# RFBoardLayoutGen0_v03_1_1_clean.net
KiCad netlist of a schematic drawn in EAGLE
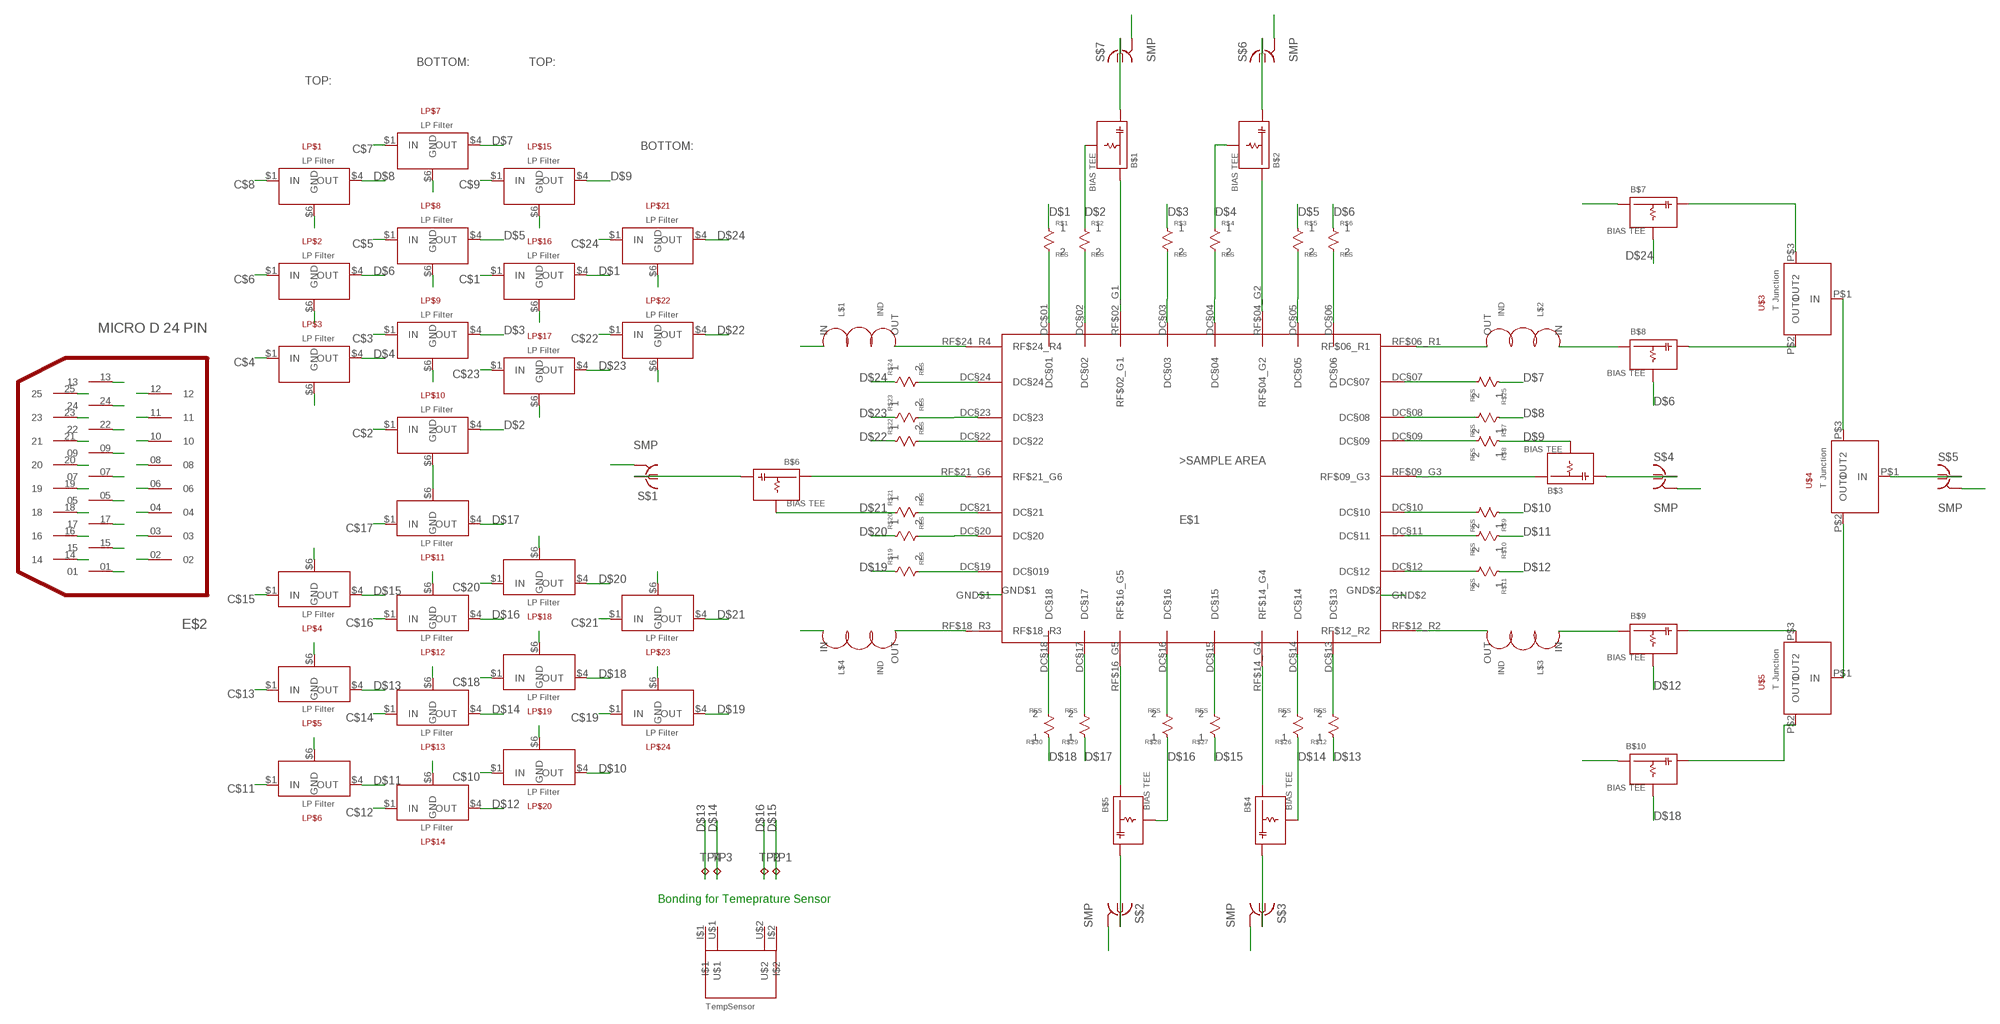
[diagram p0: schematic, sheet 1, part 1 of 2]
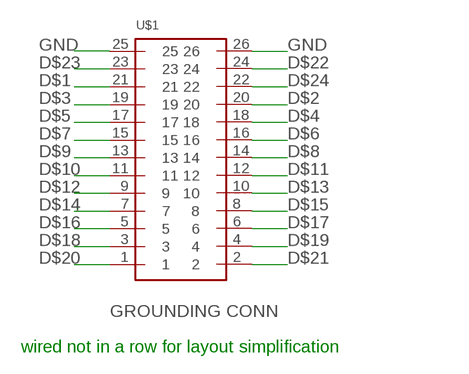
[diagram p1: schematic, sheet 1, part 2 of 2]

(export (version "E")
  (design (tool "Eeschema 10.0.6"))
  (components
    (comp (ref "B$1")
      (value "BIASTEEDOWN")
      (footprint "eagle-import:BIAS_TEE_DOWN_0603")
      (libsource (lib "eagle-import") (part "BIASTEEDOWN"))
    )
    (comp (ref "B$2")
      (value "BIASTEEUP")
      (footprint "eagle-import:BIAS_TEE_UP_0603")
      (libsource (lib "eagle-import") (part "BIASTEEUP"))
    )
    (comp (ref "B$3")
      (value "BIASTEEDOWN")
      (footprint "eagle-import:BIAS_TEE_DOWN_0603")
      (libsource (lib "eagle-import") (part "BIASTEEDOWN"))
    )
    (comp (ref "B$4")
      (value "BIASTEEDOWN")
      (footprint "eagle-import:BIAS_TEE_DOWN_0603")
      (libsource (lib "eagle-import") (part "BIASTEEDOWN"))
    )
    (comp (ref "B$5")
      (value "BIASTEEUP")
      (footprint "eagle-import:BIAS_TEE_UP_0603")
      (libsource (lib "eagle-import") (part "BIASTEEUP"))
    )
    (comp (ref "B$6")
      (value "BIASTEEDOWN")
      (footprint "eagle-import:BIAS_TEE_DOWN_0603")
      (libsource (lib "eagle-import") (part "BIASTEEDOWN"))
    )
    (comp (ref "B$7")
      (value "BIASTEEUP")
      (footprint "eagle-import:BIAS_TEE_UP_0603")
      (libsource (lib "eagle-import") (part "BIASTEEUP"))
    )
    (comp (ref "B$8")
      (value "BIASTEEDOWN")
      (footprint "eagle-import:BIAS_TEE_DOWN_0603")
      (libsource (lib "eagle-import") (part "BIASTEEDOWN"))
    )
    (comp (ref "B$9")
      (value "BIASTEEUP")
      (footprint "eagle-import:BIAS_TEE_UP_0603")
      (libsource (lib "eagle-import") (part "BIASTEEUP"))
    )
    (comp (ref "B$10")
      (value "BIASTEEDOWN")
      (footprint "eagle-import:BIAS_TEE_DOWN_0603")
      (libsource (lib "eagle-import") (part "BIASTEEDOWN"))
    )
    (comp (ref "E$1")
      (value "24DC+10RF")
      (footprint "eagle-import:24DC+10RF_400MU-PADS_0.7X0.7_V1.0")
      (libsource (lib "eagle-import") (part "24DC+10RF"))
    )
    (comp (ref "E$2")
      (value "25_SOCKET_M83513(13-DPINOUT2")
      (footprint "eagle-import:25_SOCKET_M83513_13-D_V2")
      (libsource (lib "eagle-import") (part "25_SOCKET_M83513(13-DPINOUT2"))
    )
    (comp (ref "L$1")
      (value "L_MATCH")
      (footprint "eagle-import:L_MATCH")
      (libsource (lib "eagle-import") (part "L_MATCH"))
    )
    (comp (ref "L$2")
      (value "L_MATCH")
      (footprint "eagle-import:L_MATCH")
      (libsource (lib "eagle-import") (part "L_MATCH"))
    )
    (comp (ref "L$3")
      (value "L_MATCH")
      (footprint "eagle-import:L_MATCH")
      (libsource (lib "eagle-import") (part "L_MATCH"))
    )
    (comp (ref "L$4")
      (value "L_MATCH")
      (footprint "eagle-import:L_MATCH")
      (libsource (lib "eagle-import") (part "L_MATCH"))
    )
    (comp (ref "LP$1")
      (value "LP-FILTER/1-STAGETOP")
      (footprint "eagle-import:LP-FILTER_1_STAGE_OS_0603_TOP")
      (libsource (lib "eagle-import") (part "LP-FILTER/1-STAGETOP"))
    )
    (comp (ref "LP$2")
      (value "LP-FILTER/1-STAGETOP")
      (footprint "eagle-import:LP-FILTER_1_STAGE_OS_0603_TOP")
      (libsource (lib "eagle-import") (part "LP-FILTER/1-STAGETOP"))
    )
    (comp (ref "LP$3")
      (value "LP-FILTER/1-STAGETOP")
      (footprint "eagle-import:LP-FILTER_1_STAGE_OS_0603_TOP")
      (libsource (lib "eagle-import") (part "LP-FILTER/1-STAGETOP"))
    )
    (comp (ref "LP$4")
      (value "LP-FILTER/1-STAGETOP")
      (footprint "eagle-import:LP-FILTER_1_STAGE_OS_0603_TOP")
      (libsource (lib "eagle-import") (part "LP-FILTER/1-STAGETOP"))
    )
    (comp (ref "LP$5")
      (value "LP-FILTER/1-STAGETOP")
      (footprint "eagle-import:LP-FILTER_1_STAGE_OS_0603_TOP")
      (libsource (lib "eagle-import") (part "LP-FILTER/1-STAGETOP"))
    )
    (comp (ref "LP$6")
      (value "LP-FILTER/1-STAGETOP")
      (footprint "eagle-import:LP-FILTER_1_STAGE_OS_0603_TOP")
      (libsource (lib "eagle-import") (part "LP-FILTER/1-STAGETOP"))
    )
    (comp (ref "LP$7")
      (value "LP-FILTER/1-STAGEBOT")
      (footprint "eagle-import:LP-FILTER_1_STAGE_OS_0603_BOTTOM")
      (libsource (lib "eagle-import") (part "LP-FILTER/1-STAGEBOT"))
    )
    (comp (ref "LP$8")
      (value "LP-FILTER/1-STAGEBOT")
      (footprint "eagle-import:LP-FILTER_1_STAGE_OS_0603_BOTTOM")
      (libsource (lib "eagle-import") (part "LP-FILTER/1-STAGEBOT"))
    )
    (comp (ref "LP$9")
      (value "LP-FILTER/1-STAGEBOT")
      (footprint "eagle-import:LP-FILTER_1_STAGE_OS_0603_BOTTOM")
      (libsource (lib "eagle-import") (part "LP-FILTER/1-STAGEBOT"))
    )
    (comp (ref "LP$10")
      (value "LP-FILTER/1-STAGEBOT")
      (footprint "eagle-import:LP-FILTER_1_STAGE_OS_0603_BOTTOM")
      (libsource (lib "eagle-import") (part "LP-FILTER/1-STAGEBOT"))
    )
    (comp (ref "LP$11")
      (value "LP-FILTER/1-STAGEBOT")
      (footprint "eagle-import:LP-FILTER_1_STAGE_OS_0603_BOTTOM")
      (libsource (lib "eagle-import") (part "LP-FILTER/1-STAGEBOT"))
    )
    (comp (ref "LP$12")
      (value "LP-FILTER/1-STAGEBOT")
      (footprint "eagle-import:LP-FILTER_1_STAGE_OS_0603_BOTTOM")
      (libsource (lib "eagle-import") (part "LP-FILTER/1-STAGEBOT"))
    )
    (comp (ref "LP$13")
      (value "LP-FILTER/1-STAGEBOT")
      (footprint "eagle-import:LP-FILTER_1_STAGE_OS_0603_BOTTOM")
      (libsource (lib "eagle-import") (part "LP-FILTER/1-STAGEBOT"))
    )
    (comp (ref "LP$14")
      (value "LP-FILTER/1-STAGEBOT")
      (footprint "eagle-import:LP-FILTER_1_STAGE_OS_0603_BOTTOM")
      (libsource (lib "eagle-import") (part "LP-FILTER/1-STAGEBOT"))
    )
    (comp (ref "LP$15")
      (value "LP-FILTER/1-STAGETOP")
      (footprint "eagle-import:LP-FILTER_1_STAGE_OS_0603_TOP")
      (libsource (lib "eagle-import") (part "LP-FILTER/1-STAGETOP"))
    )
    (comp (ref "LP$16")
      (value "LP-FILTER/1-STAGETOP")
      (footprint "eagle-import:LP-FILTER_1_STAGE_OS_0603_TOP")
      (libsource (lib "eagle-import") (part "LP-FILTER/1-STAGETOP"))
    )
    (comp (ref "LP$17")
      (value "LP-FILTER/1-STAGETOP")
      (footprint "eagle-import:LP-FILTER_1_STAGE_OS_0603_TOP")
      (libsource (lib "eagle-import") (part "LP-FILTER/1-STAGETOP"))
    )
    (comp (ref "LP$18")
      (value "LP-FILTER/1-STAGETOP")
      (footprint "eagle-import:LP-FILTER_1_STAGE_OS_0603_TOP")
      (libsource (lib "eagle-import") (part "LP-FILTER/1-STAGETOP"))
    )
    (comp (ref "LP$19")
      (value "LP-FILTER/1-STAGETOP")
      (footprint "eagle-import:LP-FILTER_1_STAGE_OS_0603_TOP")
      (libsource (lib "eagle-import") (part "LP-FILTER/1-STAGETOP"))
    )
    (comp (ref "LP$20")
      (value "LP-FILTER/1-STAGETOP")
      (footprint "eagle-import:LP-FILTER_1_STAGE_OS_0603_TOP")
      (libsource (lib "eagle-import") (part "LP-FILTER/1-STAGETOP"))
    )
    (comp (ref "LP$21")
      (value "LP-FILTER/1-STAGEBOT")
      (footprint "eagle-import:LP-FILTER_1_STAGE_OS_0603_BOTTOM")
      (libsource (lib "eagle-import") (part "LP-FILTER/1-STAGEBOT"))
    )
    (comp (ref "LP$22")
      (value "LP-FILTER/1-STAGEBOT")
      (footprint "eagle-import:LP-FILTER_1_STAGE_OS_0603_BOTTOM")
      (libsource (lib "eagle-import") (part "LP-FILTER/1-STAGEBOT"))
    )
    (comp (ref "LP$23")
      (value "LP-FILTER/1-STAGEBOT")
      (footprint "eagle-import:LP-FILTER_1_STAGE_OS_0603_BOTTOM")
      (libsource (lib "eagle-import") (part "LP-FILTER/1-STAGEBOT"))
    )
    (comp (ref "LP$24")
      (value "LP-FILTER/1-STAGEBOT")
      (footprint "eagle-import:LP-FILTER_1_STAGE_OS_0603_BOTTOM")
      (libsource (lib "eagle-import") (part "LP-FILTER/1-STAGEBOT"))
    )
    (comp (ref "R$1")
      (value "10K")
      (footprint "eagle-import:LP-FILTER_RESISTOR_0603_BOTTOM")
      (libsource (lib "eagle-import") (part "LP-FILTER/RESISTOR/0603"))
    )
    (comp (ref "R$2")
      (value "10K")
      (footprint "eagle-import:LP-FILTER_RESISTOR_0603_BOTTOM")
      (libsource (lib "eagle-import") (part "LP-FILTER/RESISTOR/0603"))
    )
    (comp (ref "R$3")
      (value "10K")
      (footprint "eagle-import:LP-FILTER_RESISTOR_0603_BOTTOM")
      (libsource (lib "eagle-import") (part "LP-FILTER/RESISTOR/0603"))
    )
    (comp (ref "R$4")
      (value "10K")
      (footprint "eagle-import:LP-FILTER_RESISTOR_0603_BOTTOM")
      (libsource (lib "eagle-import") (part "LP-FILTER/RESISTOR/0603"))
    )
    (comp (ref "R$5")
      (value "10K")
      (footprint "eagle-import:LP-FILTER_RESISTOR_0603_BOTTOM")
      (libsource (lib "eagle-import") (part "LP-FILTER/RESISTOR/0603"))
    )
    (comp (ref "R$6")
      (value "10K")
      (footprint "eagle-import:LP-FILTER_RESISTOR_0603_BOTTOM")
      (libsource (lib "eagle-import") (part "LP-FILTER/RESISTOR/0603"))
    )
    (comp (ref "R$7")
      (value "10K")
      (footprint "eagle-import:LP-FILTER_RESISTOR_0603_BOTTOM")
      (libsource (lib "eagle-import") (part "LP-FILTER/RESISTOR/0603"))
    )
    (comp (ref "R$8")
      (value "10K")
      (footprint "eagle-import:LP-FILTER_RESISTOR_0603_BOTTOM")
      (libsource (lib "eagle-import") (part "LP-FILTER/RESISTOR/0603"))
    )
    (comp (ref "R$9")
      (value "10K")
      (footprint "eagle-import:LP-FILTER_RESISTOR_0603_BOTTOM")
      (libsource (lib "eagle-import") (part "LP-FILTER/RESISTOR/0603"))
    )
    (comp (ref "R$10")
      (value "10K")
      (footprint "eagle-import:LP-FILTER_RESISTOR_0603_BOTTOM")
      (libsource (lib "eagle-import") (part "LP-FILTER/RESISTOR/0603"))
    )
    (comp (ref "R$11")
      (value "10K")
      (footprint "eagle-import:LP-FILTER_RESISTOR_0603_BOTTOM")
      (libsource (lib "eagle-import") (part "LP-FILTER/RESISTOR/0603"))
    )
    (comp (ref "R$12")
      (value "10K")
      (footprint "eagle-import:LP-FILTER_RESISTOR_0603_BOTTOM")
      (libsource (lib "eagle-import") (part "LP-FILTER/RESISTOR/0603"))
    )
    (comp (ref "R$19")
      (value "10K")
      (footprint "eagle-import:LP-FILTER_RESISTOR_0603_BOTTOM")
      (libsource (lib "eagle-import") (part "LP-FILTER/RESISTOR/0603"))
    )
    (comp (ref "R$20")
      (value "10K")
      (footprint "eagle-import:LP-FILTER_RESISTOR_0603_BOTTOM")
      (libsource (lib "eagle-import") (part "LP-FILTER/RESISTOR/0603"))
    )
    (comp (ref "R$21")
      (value "10K")
      (footprint "eagle-import:LP-FILTER_RESISTOR_0603_BOTTOM")
      (libsource (lib "eagle-import") (part "LP-FILTER/RESISTOR/0603"))
    )
    (comp (ref "R$22")
      (value "10K")
      (footprint "eagle-import:LP-FILTER_RESISTOR_0603_BOTTOM")
      (libsource (lib "eagle-import") (part "LP-FILTER/RESISTOR/0603"))
    )
    (comp (ref "R$23")
      (value "10K")
      (footprint "eagle-import:LP-FILTER_RESISTOR_0603_BOTTOM")
      (libsource (lib "eagle-import") (part "LP-FILTER/RESISTOR/0603"))
    )
    (comp (ref "R$24")
      (value "10K")
      (footprint "eagle-import:LP-FILTER_RESISTOR_0603_BOTTOM")
      (libsource (lib "eagle-import") (part "LP-FILTER/RESISTOR/0603"))
    )
    (comp (ref "R$25")
      (value "10K")
      (footprint "eagle-import:LP-FILTER_RESISTOR_0603_BOTTOM")
      (libsource (lib "eagle-import") (part "LP-FILTER/RESISTOR/0603"))
    )
    (comp (ref "R$26")
      (value "10K")
      (footprint "eagle-import:LP-FILTER_RESISTOR_0603_BOTTOM")
      (libsource (lib "eagle-import") (part "LP-FILTER/RESISTOR/0603"))
    )
    (comp (ref "R$27")
      (value "10K")
      (footprint "eagle-import:LP-FILTER_RESISTOR_0603_BOTTOM")
      (libsource (lib "eagle-import") (part "LP-FILTER/RESISTOR/0603"))
    )
    (comp (ref "R$28")
      (value "10K")
      (footprint "eagle-import:LP-FILTER_RESISTOR_0603_BOTTOM")
      (libsource (lib "eagle-import") (part "LP-FILTER/RESISTOR/0603"))
    )
    (comp (ref "R$29")
      (value "10K")
      (footprint "eagle-import:LP-FILTER_RESISTOR_0603_BOTTOM")
      (libsource (lib "eagle-import") (part "LP-FILTER/RESISTOR/0603"))
    )
    (comp (ref "R$30")
      (value "10K")
      (footprint "eagle-import:LP-FILTER_RESISTOR_0603_BOTTOM")
      (libsource (lib "eagle-import") (part "LP-FILTER/RESISTOR/0603"))
    )
    (comp (ref "S$1")
      (value "MC-921")
      (footprint "eagle-import:SMP_STRAIGHT_MINI")
      (libsource (lib "eagle-import") (part "MC-921"))
    )
    (comp (ref "S$2")
      (value "MC-921")
      (footprint "eagle-import:SMP_STRAIGHT_MINI")
      (libsource (lib "eagle-import") (part "MC-921"))
    )
    (comp (ref "S$3")
      (value "MC-921")
      (footprint "eagle-import:SMP_STRAIGHT_MINI")
      (libsource (lib "eagle-import") (part "MC-921"))
    )
    (comp (ref "S$4")
      (value "MC-921")
      (footprint "eagle-import:SMP_STRAIGHT_MINI")
      (libsource (lib "eagle-import") (part "MC-921"))
    )
    (comp (ref "S$5")
      (value "MC-921")
      (footprint "eagle-import:SMP_STRAIGHT_MINI")
      (libsource (lib "eagle-import") (part "MC-921"))
    )
    (comp (ref "S$6")
      (value "MC-921")
      (footprint "eagle-import:SMP_STRAIGHT_MINI")
      (libsource (lib "eagle-import") (part "MC-921"))
    )
    (comp (ref "S$7")
      (value "MC-921")
      (footprint "eagle-import:SMP_STRAIGHT_MINI")
      (libsource (lib "eagle-import") (part "MC-921"))
    )
    (comp (ref "TP1")
      (value "TPTP07SQ")
      (footprint "eagle-import:TP07SQ")
      (libsource (lib "eagle-import") (part "TPTP07SQ"))
    )
    (comp (ref "TP2")
      (value "TPTP07SQ")
      (footprint "eagle-import:TP07SQ")
      (libsource (lib "eagle-import") (part "TPTP07SQ"))
    )
    (comp (ref "TP3")
      (value "TPTP07SQ")
      (footprint "eagle-import:TP07SQ")
      (libsource (lib "eagle-import") (part "TPTP07SQ"))
    )
    (comp (ref "TP4")
      (value "TPTP07SQ")
      (footprint "eagle-import:TP07SQ")
      (libsource (lib "eagle-import") (part "TPTP07SQ"))
    )
    (comp (ref "U$1")
      (value "MEC8-113-02-L-D-RA1MBRD")
      (footprint "eagle-import:MEC8-113-02-L-D-RA1")
      (libsource (lib "eagle-import") (part "MEC8-113-02-L-D-RA1MBRD"))
    )
    (comp (ref "U$2")
      (value "TEMPSENS")
      (footprint "eagle-import:RX-BR_V1")
      (libsource (lib "eagle-import") (part "TEMPSENS"))
    )
    (comp (ref "U$3")
      (value "TJUNCTION")
      (footprint "eagle-import:T_JUNCTION_0.3MM")
      (libsource (lib "eagle-import") (part "TJUNCTION"))
    )
    (comp (ref "U$4")
      (value "TJUNCTION")
      (footprint "eagle-import:T_JUNCTION_0.3MM")
      (libsource (lib "eagle-import") (part "TJUNCTION"))
    )
    (comp (ref "U$5")
      (value "TJUNCTION")
      (footprint "eagle-import:T_JUNCTION_0.3MM")
      (libsource (lib "eagle-import") (part "TJUNCTION"))
    )
  )
  (nets
    (net (code "1") (name "/C$1") (class "Default")
      (node (ref "E$2") (pin "01") (pinfunction "01_01") (pintype "bidirectional"))
      (node (ref "LP$16") (pin "$1") (pinfunction "IN_$1") (pintype "bidirectional"))
    )
    (net (code "2") (name "/C$2") (class "Default")
      (node (ref "E$2") (pin "02") (pinfunction "02_02") (pintype "bidirectional"))
      (node (ref "LP$10") (pin "$1") (pinfunction "IN_$1") (pintype "bidirectional"))
    )
    (net (code "3") (name "/C$3") (class "Default")
      (node (ref "E$2") (pin "03") (pinfunction "03_03") (pintype "bidirectional"))
      (node (ref "LP$9") (pin "$1") (pinfunction "IN_$1") (pintype "bidirectional"))
    )
    (net (code "4") (name "/C$4") (class "Default")
      (node (ref "E$2") (pin "04") (pinfunction "04_04") (pintype "bidirectional"))
      (node (ref "LP$3") (pin "$1") (pinfunction "IN_$1") (pintype "bidirectional"))
    )
    (net (code "5") (name "/C$5") (class "Default")
      (node (ref "E$2") (pin "05") (pinfunction "05_05") (pintype "bidirectional"))
      (node (ref "LP$8") (pin "$1") (pinfunction "IN_$1") (pintype "bidirectional"))
    )
    (net (code "6") (name "/C$6") (class "Default")
      (node (ref "E$2") (pin "06") (pinfunction "06_06") (pintype "bidirectional"))
      (node (ref "LP$2") (pin "$1") (pinfunction "IN_$1") (pintype "bidirectional"))
    )
    (net (code "7") (name "/C$7") (class "Default")
      (node (ref "E$2") (pin "07") (pinfunction "07_07") (pintype "bidirectional"))
      (node (ref "LP$7") (pin "$1") (pinfunction "IN_$1") (pintype "bidirectional"))
    )
    (net (code "8") (name "/C$8") (class "Default")
      (node (ref "E$2") (pin "08") (pinfunction "08_08") (pintype "bidirectional"))
      (node (ref "LP$1") (pin "$1") (pinfunction "IN_$1") (pintype "bidirectional"))
    )
    (net (code "9") (name "/C$9") (class "Default")
      (node (ref "E$2") (pin "09") (pinfunction "09_09") (pintype "bidirectional"))
      (node (ref "LP$15") (pin "$1") (pinfunction "IN_$1") (pintype "bidirectional"))
    )
    (net (code "10") (name "/C$10") (class "Default")
      (node (ref "E$2") (pin "10") (pinfunction "10_10") (pintype "bidirectional"))
      (node (ref "LP$20") (pin "$1") (pinfunction "IN_$1") (pintype "bidirectional"))
    )
    (net (code "11") (name "/C$11") (class "Default")
      (node (ref "E$2") (pin "11") (pinfunction "11_11") (pintype "bidirectional"))
      (node (ref "LP$6") (pin "$1") (pinfunction "IN_$1") (pintype "bidirectional"))
    )
    (net (code "12") (name "/C$12") (class "Default")
      (node (ref "E$2") (pin "12") (pinfunction "12_12") (pintype "bidirectional"))
      (node (ref "LP$14") (pin "$1") (pinfunction "IN_$1") (pintype "bidirectional"))
    )
    (net (code "13") (name "/C$13") (class "Default")
      (node (ref "E$2") (pin "13") (pinfunction "13_13") (pintype "bidirectional"))
      (node (ref "LP$5") (pin "$1") (pinfunction "IN_$1") (pintype "bidirectional"))
    )
    (net (code "14") (name "/C$14") (class "Default")
      (node (ref "E$2") (pin "14") (pinfunction "14_14") (pintype "bidirectional"))
      (node (ref "LP$13") (pin "$1") (pinfunction "IN_$1") (pintype "bidirectional"))
    )
    (net (code "15") (name "/C$15") (class "Default")
      (node (ref "E$2") (pin "15") (pinfunction "15_15") (pintype "bidirectional"))
      (node (ref "LP$4") (pin "$1") (pinfunction "IN_$1") (pintype "bidirectional"))
    )
    (net (code "16") (name "/C$16") (class "Default")
      (node (ref "E$2") (pin "16") (pinfunction "16_16") (pintype "bidirectional"))
      (node (ref "LP$12") (pin "$1") (pinfunction "IN_$1") (pintype "bidirectional"))
    )
    (net (code "17") (name "/C$17") (class "Default")
      (node (ref "E$2") (pin "17") (pinfunction "17_17") (pintype "bidirectional"))
      (node (ref "LP$11") (pin "$1") (pinfunction "IN_$1") (pintype "bidirectional"))
    )
    (net (code "18") (name "/C$18") (class "Default")
      (node (ref "E$2") (pin "18") (pinfunction "18_18") (pintype "bidirectional"))
      (node (ref "LP$19") (pin "$1") (pinfunction "IN_$1") (pintype "bidirectional"))
    )
    (net (code "19") (name "/C$19") (class "Default")
      (node (ref "E$2") (pin "19") (pinfunction "19_19") (pintype "bidirectional"))
      (node (ref "LP$24") (pin "$1") (pinfunction "IN_$1") (pintype "bidirectional"))
    )
    (net (code "20") (name "/C$20") (class "Default")
      (node (ref "E$2") (pin "20") (pinfunction "20_20") (pintype "bidirectional"))
      (node (ref "LP$18") (pin "$1") (pinfunction "IN_$1") (pintype "bidirectional"))
    )
    (net (code "21") (name "/C$21") (class "Default")
      (node (ref "E$2") (pin "21") (pinfunction "21_21") (pintype "bidirectional"))
      (node (ref "LP$23") (pin "$1") (pinfunction "IN_$1") (pintype "bidirectional"))
    )
    (net (code "22") (name "/C$22") (class "Default")
      (node (ref "E$2") (pin "22") (pinfunction "22_22") (pintype "bidirectional"))
      (node (ref "LP$22") (pin "$1") (pinfunction "IN_$1") (pintype "bidirectional"))
    )
    (net (code "23") (name "/C$23") (class "Default")
      (node (ref "E$2") (pin "23") (pinfunction "23_23") (pintype "bidirectional"))
      (node (ref "LP$17") (pin "$1") (pinfunction "IN_$1") (pintype "bidirectional"))
    )
    (net (code "24") (name "/C$24") (class "Default")
      (node (ref "E$2") (pin "24") (pinfunction "24_24") (pintype "bidirectional"))
      (node (ref "LP$21") (pin "$1") (pinfunction "IN_$1") (pintype "bidirectional"))
    )
    (net (code "25") (name "/D$1") (class "Default")
      (node (ref "LP$16") (pin "$4") (pinfunction "OUT_$4") (pintype "bidirectional"))
      (node (ref "R$1") (pin "IN") (pinfunction "1_IN") (pintype "passive"))
      (node (ref "U$1") (pin "21") (pinfunction "21_21") (pintype "bidirectional"))
    )
    (net (code "26") (name "/D$2") (class "Default")
      (node (ref "B$1") (pin "LF") (pinfunction "LF_LF") (pintype "bidirectional"))
      (node (ref "LP$10") (pin "$4") (pinfunction "OUT_$4") (pintype "bidirectional"))
      (node (ref "R$2") (pin "IN") (pinfunction "1_IN") (pintype "passive"))
      (node (ref "U$1") (pin "20") (pinfunction "20_20") (pintype "bidirectional"))
    )
    (net (code "27") (name "/D$3") (class "Default")
      (node (ref "LP$9") (pin "$4") (pinfunction "OUT_$4") (pintype "bidirectional"))
      (node (ref "R$3") (pin "IN") (pinfunction "1_IN") (pintype "passive"))
      (node (ref "U$1") (pin "19") (pinfunction "19_19") (pintype "bidirectional"))
    )
    (net (code "28") (name "/D$4") (class "Default")
      (node (ref "B$2") (pin "LF") (pinfunction "LF_LF") (pintype "bidirectional"))
      (node (ref "LP$3") (pin "$4") (pinfunction "OUT_$4") (pintype "bidirectional"))
      (node (ref "R$4") (pin "IN") (pinfunction "1_IN") (pintype "passive"))
      (node (ref "U$1") (pin "18") (pinfunction "18_18") (pintype "bidirectional"))
    )
    (net (code "29") (name "/D$5") (class "Default")
      (node (ref "LP$8") (pin "$4") (pinfunction "OUT_$4") (pintype "bidirectional"))
      (node (ref "R$5") (pin "IN") (pinfunction "1_IN") (pintype "passive"))
      (node (ref "U$1") (pin "17") (pinfunction "17_17") (pintype "bidirectional"))
    )
    (net (code "30") (name "/D$6") (class "Default")
      (node (ref "B$8") (pin "LF") (pinfunction "LF_LF") (pintype "bidirectional"))
      (node (ref "LP$2") (pin "$4") (pinfunction "OUT_$4") (pintype "bidirectional"))
      (node (ref "R$6") (pin "IN") (pinfunction "1_IN") (pintype "passive"))
      (node (ref "U$1") (pin "16") (pinfunction "16_16") (pintype "bidirectional"))
    )
    (net (code "31") (name "/D$7") (class "Default")
      (node (ref "LP$7") (pin "$4") (pinfunction "OUT_$4") (pintype "bidirectional"))
      (node (ref "R$25") (pin "IN") (pinfunction "1_IN") (pintype "passive"))
      (node (ref "U$1") (pin "15") (pinfunction "15_15") (pintype "bidirectional"))
    )
    (net (code "32") (name "/D$8") (class "Default")
      (node (ref "LP$1") (pin "$4") (pinfunction "OUT_$4") (pintype "bidirectional"))
      (node (ref "R$7") (pin "IN") (pinfunction "1_IN") (pintype "passive"))
      (node (ref "U$1") (pin "14") (pinfunction "14_14") (pintype "bidirectional"))
    )
    (net (code "33") (name "/D$9") (class "Default")
      (node (ref "B$3") (pin "LF") (pinfunction "LF_LF") (pintype "bidirectional"))
      (node (ref "LP$15") (pin "$4") (pinfunction "OUT_$4") (pintype "bidirectional"))
      (node (ref "R$8") (pin "IN") (pinfunction "1_IN") (pintype "passive"))
      (node (ref "U$1") (pin "13") (pinfunction "13_13") (pintype "bidirectional"))
    )
    (net (code "34") (name "/D$10") (class "Default")
      (node (ref "LP$20") (pin "$4") (pinfunction "OUT_$4") (pintype "bidirectional"))
      (node (ref "R$9") (pin "IN") (pinfunction "1_IN") (pintype "passive"))
      (node (ref "U$1") (pin "11") (pinfunction "11_11") (pintype "bidirectional"))
    )
    (net (code "35") (name "/D$11") (class "Default")
      (node (ref "LP$6") (pin "$4") (pinfunction "OUT_$4") (pintype "bidirectional"))
      (node (ref "R$10") (pin "IN") (pinfunction "1_IN") (pintype "passive"))
      (node (ref "U$1") (pin "12") (pinfunction "12_12") (pintype "bidirectional"))
    )
    (net (code "36") (name "/D$12") (class "Default")
      (node (ref "B$9") (pin "LF") (pinfunction "LF_LF") (pintype "bidirectional"))
      (node (ref "LP$14") (pin "$4") (pinfunction "OUT_$4") (pintype "bidirectional"))
      (node (ref "R$11") (pin "IN") (pinfunction "1_IN") (pintype "passive"))
      (node (ref "U$1") (pin "9") (pinfunction "9_9") (pintype "bidirectional"))
    )
    (net (code "37") (name "/D$13") (class "Default")
      (node (ref "LP$5") (pin "$4") (pinfunction "OUT_$4") (pintype "bidirectional"))
      (node (ref "R$12") (pin "IN") (pinfunction "1_IN") (pintype "passive"))
      (node (ref "TP4") (pin "TP") (pinfunction "TP_TP") (pintype "input"))
      (node (ref "U$1") (pin "10") (pinfunction "10_10") (pintype "bidirectional"))
    )
    (net (code "38") (name "/D$14") (class "Default")
      (node (ref "B$4") (pin "LF") (pinfunction "LF_LF") (pintype "bidirectional"))
      (node (ref "LP$13") (pin "$4") (pinfunction "OUT_$4") (pintype "bidirectional"))
      (node (ref "R$26") (pin "IN") (pinfunction "1_IN") (pintype "passive"))
      (node (ref "TP3") (pin "TP") (pinfunction "TP_TP") (pintype "input"))
      (node (ref "U$1") (pin "7") (pinfunction "7_7") (pintype "bidirectional"))
    )
    (net (code "39") (name "/D$15") (class "Default")
      (node (ref "LP$4") (pin "$4") (pinfunction "OUT_$4") (pintype "bidirectional"))
      (node (ref "R$27") (pin "IN") (pinfunction "1_IN") (pintype "passive"))
      (node (ref "TP1") (pin "TP") (pinfunction "TP_TP") (pintype "input"))
      (node (ref "U$1") (pin "8") (pinfunction "8_8") (pintype "bidirectional"))
    )
    (net (code "40") (name "/D$16") (class "Default")
      (node (ref "B$5") (pin "LF") (pinfunction "LF_LF") (pintype "bidirectional"))
      (node (ref "LP$12") (pin "$4") (pinfunction "OUT_$4") (pintype "bidirectional"))
      (node (ref "R$28") (pin "IN") (pinfunction "1_IN") (pintype "passive"))
      (node (ref "TP2") (pin "TP") (pinfunction "TP_TP") (pintype "input"))
      (node (ref "U$1") (pin "5") (pinfunction "5_5") (pintype "bidirectional"))
    )
    (net (code "41") (name "/D$17") (class "Default")
      (node (ref "LP$11") (pin "$4") (pinfunction "OUT_$4") (pintype "bidirectional"))
      (node (ref "R$29") (pin "IN") (pinfunction "1_IN") (pintype "passive"))
      (node (ref "U$1") (pin "6") (pinfunction "6_6") (pintype "bidirectional"))
    )
    (net (code "42") (name "/D$18") (class "Default")
      (node (ref "B$10") (pin "LF") (pinfunction "LF_LF") (pintype "bidirectional"))
      (node (ref "LP$19") (pin "$4") (pinfunction "OUT_$4") (pintype "bidirectional"))
      (node (ref "R$30") (pin "IN") (pinfunction "1_IN") (pintype "passive"))
      (node (ref "U$1") (pin "3") (pinfunction "3_3") (pintype "bidirectional"))
    )
    (net (code "43") (name "/D$19") (class "Default")
      (node (ref "LP$24") (pin "$4") (pinfunction "OUT_$4") (pintype "bidirectional"))
      (node (ref "R$19") (pin "IN") (pinfunction "1_IN") (pintype "passive"))
      (node (ref "U$1") (pin "4") (pinfunction "4_4") (pintype "bidirectional"))
    )
    (net (code "44") (name "/D$20") (class "Default")
      (node (ref "LP$18") (pin "$4") (pinfunction "OUT_$4") (pintype "bidirectional"))
      (node (ref "R$20") (pin "IN") (pinfunction "1_IN") (pintype "passive"))
      (node (ref "U$1") (pin "1") (pinfunction "1_1") (pintype "bidirectional"))
    )
    (net (code "45") (name "/D$21") (class "Default")
      (node (ref "B$6") (pin "LF") (pinfunction "LF_LF") (pintype "bidirectional"))
      (node (ref "LP$23") (pin "$4") (pinfunction "OUT_$4") (pintype "bidirectional"))
      (node (ref "R$21") (pin "IN") (pinfunction "1_IN") (pintype "passive"))
      (node (ref "U$1") (pin "2") (pinfunction "2_2") (pintype "bidirectional"))
    )
    (net (code "46") (name "/D$22") (class "Default")
      (node (ref "LP$22") (pin "$4") (pinfunction "OUT_$4") (pintype "bidirectional"))
      (node (ref "R$22") (pin "IN") (pinfunction "1_IN") (pintype "passive"))
      (node (ref "U$1") (pin "24") (pinfunction "24_24") (pintype "bidirectional"))
    )
    (net (code "47") (name "/D$23") (class "Default")
      (node (ref "LP$17") (pin "$4") (pinfunction "OUT_$4") (pintype "bidirectional"))
      (node (ref "R$23") (pin "IN") (pinfunction "1_IN") (pintype "passive"))
      (node (ref "U$1") (pin "23") (pinfunction "23_23") (pintype "bidirectional"))
    )
    (net (code "48") (name "/D$24") (class "Default")
      (node (ref "B$7") (pin "LF") (pinfunction "LF_LF") (pintype "bidirectional"))
      (node (ref "LP$21") (pin "$4") (pinfunction "OUT_$4") (pintype "bidirectional"))
      (node (ref "R$24") (pin "IN") (pinfunction "1_IN") (pintype "passive"))
      (node (ref "U$1") (pin "22") (pinfunction "22_22") (pintype "bidirectional"))
    )
    (net (code "49") (name "/GND") (class "Default")
      (node (ref "E$1") (pin "GND$1") (pinfunction "GND$1_GND$1") (pintype "bidirectional"))
      (node (ref "E$1") (pin "GND$2") (pinfunction "GND$2_GND$2") (pintype "bidirectional"))
      (node (ref "E$2") (pin "25") (pinfunction "25_25") (pintype "bidirectional"))
      (node (ref "LP$1") (pin "$6") (pinfunction "GND_$6") (pintype "bidirectional"))
      (node (ref "LP$10") (pin "$6") (pinfunction "GND_$6") (pintype "bidirectional"))
      (node (ref "LP$11") (pin "$6") (pinfunction "GND_$6") (pintype "bidirectional"))
      (node (ref "LP$12") (pin "$6") (pinfunction "GND_$6") (pintype "bidirectional"))
      (node (ref "LP$13") (pin "$6") (pinfunction "GND_$6") (pintype "bidirectional"))
      (node (ref "LP$14") (pin "$6") (pinfunction "GND_$6") (pintype "bidirectional"))
      (node (ref "LP$15") (pin "$6") (pinfunction "GND_$6") (pintype "bidirectional"))
      (node (ref "LP$16") (pin "$6") (pinfunction "GND_$6") (pintype "bidirectional"))
      (node (ref "LP$17") (pin "$6") (pinfunction "GND_$6") (pintype "bidirectional"))
      (node (ref "LP$18") (pin "$6") (pinfunction "GND_$6") (pintype "bidirectional"))
      (node (ref "LP$19") (pin "$6") (pinfunction "GND_$6") (pintype "bidirectional"))
      (node (ref "LP$2") (pin "$6") (pinfunction "GND_$6") (pintype "bidirectional"))
      (node (ref "LP$20") (pin "$6") (pinfunction "GND_$6") (pintype "bidirectional"))
      (node (ref "LP$21") (pin "$6") (pinfunction "GND_$6") (pintype "bidirectional"))
      (node (ref "LP$22") (pin "$6") (pinfunction "GND_$6") (pintype "bidirectional"))
      (node (ref "LP$23") (pin "$6") (pinfunction "GND_$6") (pintype "bidirectional"))
      (node (ref "LP$24") (pin "$6") (pinfunction "GND_$6") (pintype "bidirectional"))
      (node (ref "LP$3") (pin "$6") (pinfunction "GND_$6") (pintype "bidirectional"))
      (node (ref "LP$4") (pin "$6") (pinfunction "GND_$6") (pintype "bidirectional"))
      (node (ref "LP$5") (pin "$6") (pinfunction "GND_$6") (pintype "bidirectional"))
      (node (ref "LP$6") (pin "$6") (pinfunction "GND_$6") (pintype "bidirectional"))
      (node (ref "LP$7") (pin "$6") (pinfunction "GND_$6") (pintype "bidirectional"))
      (node (ref "LP$8") (pin "$6") (pinfunction "GND_$6") (pintype "bidirectional"))
      (node (ref "LP$9") (pin "$6") (pinfunction "GND_$6") (pintype "bidirectional"))
      (node (ref "S$1") (pin "2@1") (pinfunction "GND_2@1") (pintype "passive"))
      (node (ref "S$1") (pin "2@2") (pinfunction "GND_2@2") (pintype "passive"))
      (node (ref "S$2") (pin "2@1") (pinfunction "GND_2@1") (pintype "passive"))
      (node (ref "S$2") (pin "2@2") (pinfunction "GND_2@2") (pintype "passive"))
      (node (ref "S$3") (pin "2@1") (pinfunction "GND_2@1") (pintype "passive"))
      (node (ref "S$3") (pin "2@2") (pinfunction "GND_2@2") (pintype "passive"))
      (node (ref "S$4") (pin "2@1") (pinfunction "GND_2@1") (pintype "passive"))
      (node (ref "S$4") (pin "2@2") (pinfunction "GND_2@2") (pintype "passive"))
      (node (ref "S$5") (pin "2@1") (pinfunction "GND_2@1") (pintype "passive"))
      (node (ref "S$5") (pin "2@2") (pinfunction "GND_2@2") (pintype "passive"))
      (node (ref "S$6") (pin "2@1") (pinfunction "GND_2@1") (pintype "passive"))
      (node (ref "S$6") (pin "2@2") (pinfunction "GND_2@2") (pintype "passive"))
      (node (ref "S$7") (pin "2@1") (pinfunction "GND_2@1") (pintype "passive"))
      (node (ref "S$7") (pin "2@2") (pinfunction "GND_2@2") (pintype "passive"))
      (node (ref "U$1") (pin "25") (pinfunction "25_25") (pintype "bidirectional"))
      (node (ref "U$1") (pin "26") (pinfunction "26_26") (pintype "bidirectional"))
    )
    (net (code "50") (name "/RF$3") (class "Default")
      (node (ref "B$10") (pin "OUT") (pinfunction "OUT_OUT") (pintype "bidirectional"))
      (node (ref "L$4") (pin "IN") (pinfunction "IN_IN") (pintype "passive"))
    )
    (net (code "51") (name "/RF$4") (class "Default")
      (node (ref "B$7") (pin "OUT") (pinfunction "OUT_OUT") (pintype "bidirectional"))
      (node (ref "L$1") (pin "IN") (pinfunction "IN_IN") (pintype "passive"))
    )
    (net (code "52") (name "Net-(B$1-PadHF)") (class "Default")
      (node (ref "B$1") (pin "HF") (pinfunction "HF_HF") (pintype "bidirectional"))
      (node (ref "S$7") (pin "1") (pinfunction "1_1") (pintype "passive"))
    )
    (net (code "53") (name "Net-(B$1-PadOUT)") (class "Default")
      (node (ref "B$1") (pin "OUT") (pinfunction "OUT_OUT") (pintype "bidirectional"))
      (node (ref "E$1") (pin "RF$02_G1") (pinfunction "RF$02_G1_RF$02_G1") (pintype "bidirectional"))
    )
    (net (code "54") (name "Net-(B$2-PadHF)") (class "Default")
      (node (ref "B$2") (pin "HF") (pinfunction "HF_HF") (pintype "bidirectional"))
      (node (ref "S$6") (pin "1") (pinfunction "1_1") (pintype "passive"))
    )
    (net (code "55") (name "Net-(B$2-PadOUT)") (class "Default")
      (node (ref "B$2") (pin "OUT") (pinfunction "OUT_OUT") (pintype "bidirectional"))
      (node (ref "E$1") (pin "RF$04_G2") (pinfunction "RF$04_G2_RF$04_G2") (pintype "bidirectional"))
    )
    (net (code "56") (name "Net-(B$3-PadHF)") (class "Default")
      (node (ref "B$3") (pin "HF") (pinfunction "HF_HF") (pintype "bidirectional"))
      (node (ref "S$4") (pin "1") (pinfunction "1_1") (pintype "passive"))
    )
    (net (code "57") (name "Net-(B$3-PadOUT)") (class "Default")
      (node (ref "B$3") (pin "OUT") (pinfunction "OUT_OUT") (pintype "bidirectional"))
      (node (ref "E$1") (pin "RF$09_G3") (pinfunction "RF$09_G3_RF$09_G3") (pintype "bidirectional"))
    )
    (net (code "58") (name "Net-(B$4-PadHF)") (class "Default")
      (node (ref "B$4") (pin "HF") (pinfunction "HF_HF") (pintype "bidirectional"))
      (node (ref "S$3") (pin "1") (pinfunction "1_1") (pintype "passive"))
    )
    (net (code "59") (name "Net-(B$4-PadOUT)") (class "Default")
      (node (ref "B$4") (pin "OUT") (pinfunction "OUT_OUT") (pintype "bidirectional"))
      (node (ref "E$1") (pin "RF$14_G4") (pinfunction "RF$14_G4_RF$14_G4") (pintype "bidirectional"))
    )
    (net (code "60") (name "Net-(B$5-PadHF)") (class "Default")
      (node (ref "B$5") (pin "HF") (pinfunction "HF_HF") (pintype "bidirectional"))
      (node (ref "S$2") (pin "1") (pinfunction "1_1") (pintype "passive"))
    )
    (net (code "61") (name "Net-(B$5-PadOUT)") (class "Default")
      (node (ref "B$5") (pin "OUT") (pinfunction "OUT_OUT") (pintype "bidirectional"))
      (node (ref "E$1") (pin "RF$16_G5") (pinfunction "RF$16_G5_RF$16_G5") (pintype "bidirectional"))
    )
    (net (code "62") (name "Net-(B$6-PadHF)") (class "Default")
      (node (ref "B$6") (pin "HF") (pinfunction "HF_HF") (pintype "bidirectional"))
      (node (ref "S$1") (pin "1") (pinfunction "1_1") (pintype "passive"))
    )
    (net (code "63") (name "Net-(B$6-PadOUT)") (class "Default")
      (node (ref "B$6") (pin "OUT") (pinfunction "OUT_OUT") (pintype "bidirectional"))
      (node (ref "E$1") (pin "RF$21_G6") (pinfunction "RF$21_G6_RF$21_G6") (pintype "bidirectional"))
    )
    (net (code "64") (name "Net-(B$8-PadOUT)") (class "Default")
      (node (ref "B$8") (pin "OUT") (pinfunction "OUT_OUT") (pintype "bidirectional"))
      (node (ref "L$2") (pin "IN") (pinfunction "IN_IN") (pintype "passive"))
    )
    (net (code "65") (name "Net-(B$9-PadOUT)") (class "Default")
      (node (ref "B$9") (pin "OUT") (pinfunction "OUT_OUT") (pintype "bidirectional"))
      (node (ref "L$3") (pin "IN") (pinfunction "IN_IN") (pintype "passive"))
    )
    (net (code "66") (name "Net-(E$1-DC§01)") (class "Default")
      (node (ref "E$1") (pin "DC$01") (pinfunction "DC§01_DC$01") (pintype "bidirectional"))
      (node (ref "R$1") (pin "OUT") (pinfunction "2_OUT") (pintype "passive"))
    )
    (net (code "67") (name "Net-(E$1-DC§019)") (class "Default")
      (node (ref "E$1") (pin "DC§19") (pinfunction "DC§019_DC§19") (pintype "bidirectional"))
      (node (ref "R$19") (pin "OUT") (pinfunction "2_OUT") (pintype "passive"))
    )
    (net (code "68") (name "Net-(E$1-PadRF$06_R1)") (class "Default")
      (node (ref "E$1") (pin "RF$06_R1") (pinfunction "RF$06_R1_RF$06_R1") (pintype "bidirectional"))
      (node (ref "L$2") (pin "OUT") (pinfunction "OUT_OUT") (pintype "passive"))
    )
    (net (code "69") (name "Net-(E$1-PadRF$12_R2)") (class "Default")
      (node (ref "E$1") (pin "RF$12_R2") (pinfunction "RF$12_R2_RF$12_R2") (pintype "bidirectional"))
      (node (ref "L$3") (pin "OUT") (pinfunction "OUT_OUT") (pintype "passive"))
    )
    (net (code "70") (name "Net-(E$1-PadRF$18_R3)") (class "Default")
      (node (ref "E$1") (pin "RF$18_R3") (pinfunction "RF$18_R3_RF$18_R3") (pintype "bidirectional"))
      (node (ref "L$4") (pin "OUT") (pinfunction "OUT_OUT") (pintype "passive"))
    )
    (net (code "71") (name "Net-(E$1-PadRF$24_R4)") (class "Default")
      (node (ref "E$1") (pin "RF$24_R4") (pinfunction "RF$24_R4_RF$24_R4") (pintype "bidirectional"))
      (node (ref "L$1") (pin "OUT") (pinfunction "OUT_OUT") (pintype "passive"))
    )
    (net (code "72") (name "Net-(R$2-2)") (class "Default")
      (node (ref "E$1") (pin "DC§02") (pinfunction "DC§02_DC§02") (pintype "bidirectional"))
      (node (ref "R$2") (pin "OUT") (pinfunction "2_OUT") (pintype "passive"))
    )
    (net (code "73") (name "Net-(R$3-2)") (class "Default")
      (node (ref "E$1") (pin "DC§03") (pinfunction "DC§03_DC§03") (pintype "bidirectional"))
      (node (ref "R$3") (pin "OUT") (pinfunction "2_OUT") (pintype "passive"))
    )
    (net (code "74") (name "Net-(R$4-2)") (class "Default")
      (node (ref "E$1") (pin "DC§04") (pinfunction "DC§04_DC§04") (pintype "bidirectional"))
      (node (ref "R$4") (pin "OUT") (pinfunction "2_OUT") (pintype "passive"))
    )
    (net (code "75") (name "Net-(R$5-2)") (class "Default")
      (node (ref "E$1") (pin "DC§05") (pinfunction "DC§05_DC§05") (pintype "bidirectional"))
      (node (ref "R$5") (pin "OUT") (pinfunction "2_OUT") (pintype "passive"))
    )
    (net (code "76") (name "Net-(R$6-2)") (class "Default")
      (node (ref "E$1") (pin "DC§06") (pinfunction "DC§06_DC§06") (pintype "bidirectional"))
      (node (ref "R$6") (pin "OUT") (pinfunction "2_OUT") (pintype "passive"))
    )
    (net (code "77") (name "Net-(R$7-2)") (class "Default")
      (node (ref "E$1") (pin "DC§08") (pinfunction "DC§08_DC§08") (pintype "bidirectional"))
      (node (ref "R$7") (pin "OUT") (pinfunction "2_OUT") (pintype "passive"))
    )
    (net (code "78") (name "Net-(R$8-2)") (class "Default")
      (node (ref "E$1") (pin "DC§09") (pinfunction "DC§09_DC§09") (pintype "bidirectional"))
      (node (ref "R$8") (pin "OUT") (pinfunction "2_OUT") (pintype "passive"))
    )
    (net (code "79") (name "Net-(R$9-2)") (class "Default")
      (node (ref "E$1") (pin "DC§10") (pinfunction "DC§10_DC§10") (pintype "bidirectional"))
      (node (ref "R$9") (pin "OUT") (pinfunction "2_OUT") (pintype "passive"))
    )
    (net (code "80") (name "Net-(R$10-2)") (class "Default")
      (node (ref "E$1") (pin "DC§11") (pinfunction "DC§11_DC§11") (pintype "bidirectional"))
      (node (ref "R$10") (pin "OUT") (pinfunction "2_OUT") (pintype "passive"))
    )
    (net (code "81") (name "Net-(R$11-2)") (class "Default")
      (node (ref "E$1") (pin "DC§12") (pinfunction "DC§12_DC§12") (pintype "bidirectional"))
      (node (ref "R$11") (pin "OUT") (pinfunction "2_OUT") (pintype "passive"))
    )
    (net (code "82") (name "Net-(R$12-2)") (class "Default")
      (node (ref "E$1") (pin "DC§13") (pinfunction "DC§13_DC§13") (pintype "bidirectional"))
      (node (ref "R$12") (pin "OUT") (pinfunction "2_OUT") (pintype "passive"))
    )
    (net (code "83") (name "Net-(R$20-2)") (class "Default")
      (node (ref "E$1") (pin "DC§20") (pinfunction "DC§20_DC§20") (pintype "bidirectional"))
      (node (ref "R$20") (pin "OUT") (pinfunction "2_OUT") (pintype "passive"))
    )
    (net (code "84") (name "Net-(R$21-2)") (class "Default")
      (node (ref "E$1") (pin "DC§21") (pinfunction "DC§21_DC§21") (pintype "bidirectional"))
      (node (ref "R$21") (pin "OUT") (pinfunction "2_OUT") (pintype "passive"))
    )
    (net (code "85") (name "Net-(R$22-2)") (class "Default")
      (node (ref "E$1") (pin "DC§22") (pinfunction "DC§22_DC§22") (pintype "bidirectional"))
      (node (ref "R$22") (pin "OUT") (pinfunction "2_OUT") (pintype "passive"))
    )
    (net (code "86") (name "Net-(R$23-2)") (class "Default")
      (node (ref "E$1") (pin "DC§23") (pinfunction "DC§23_DC§23") (pintype "bidirectional"))
      (node (ref "R$23") (pin "OUT") (pinfunction "2_OUT") (pintype "passive"))
    )
    (net (code "87") (name "Net-(R$24-2)") (class "Default")
      (node (ref "E$1") (pin "DC§24") (pinfunction "DC§24_DC§24") (pintype "bidirectional"))
      (node (ref "R$24") (pin "OUT") (pinfunction "2_OUT") (pintype "passive"))
    )
    (net (code "88") (name "Net-(R$25-2)") (class "Default")
      (node (ref "E$1") (pin "DC§07") (pinfunction "DC§07_DC§07") (pintype "bidirectional"))
      (node (ref "R$25") (pin "OUT") (pinfunction "2_OUT") (pintype "passive"))
    )
    (net (code "89") (name "Net-(R$26-2)") (class "Default")
      (node (ref "E$1") (pin "DC§14") (pinfunction "DC§14_DC§14") (pintype "bidirectional"))
      (node (ref "R$26") (pin "OUT") (pinfunction "2_OUT") (pintype "passive"))
    )
    (net (code "90") (name "Net-(R$27-2)") (class "Default")
      (node (ref "E$1") (pin "DC§15") (pinfunction "DC§15_DC§15") (pintype "bidirectional"))
      (node (ref "R$27") (pin "OUT") (pinfunction "2_OUT") (pintype "passive"))
    )
    (net (code "91") (name "Net-(R$28-2)") (class "Default")
      (node (ref "E$1") (pin "DC§16") (pinfunction "DC§16_DC§16") (pintype "bidirectional"))
      (node (ref "R$28") (pin "OUT") (pinfunction "2_OUT") (pintype "passive"))
    )
    (net (code "92") (name "Net-(R$29-2)") (class "Default")
      (node (ref "E$1") (pin "DC§17") (pinfunction "DC§17_DC§17") (pintype "bidirectional"))
      (node (ref "R$29") (pin "OUT") (pinfunction "2_OUT") (pintype "passive"))
    )
    (net (code "93") (name "Net-(R$30-2)") (class "Default")
      (node (ref "E$1") (pin "DC§18") (pinfunction "DC§18_DC§18") (pintype "bidirectional"))
      (node (ref "R$30") (pin "OUT") (pinfunction "2_OUT") (pintype "passive"))
    )
    (net (code "94") (name "Net-(U$3-IN)") (class "Default")
      (node (ref "U$3") (pin "P$1") (pinfunction "IN_P$1") (pintype "bidirectional"))
      (node (ref "U$4") (pin "P$3") (pinfunction "OUT2_P$3") (pintype "bidirectional"))
    )
    (net (code "95") (name "Net-(U$3-OUT1)") (class "Default")
      (node (ref "B$8") (pin "HF") (pinfunction "HF_HF") (pintype "bidirectional"))
      (node (ref "U$3") (pin "P$2") (pinfunction "OUT1_P$2") (pintype "bidirectional"))
    )
    (net (code "96") (name "Net-(U$3-OUT2)") (class "Default")
      (node (ref "B$7") (pin "HF") (pinfunction "HF_HF") (pintype "bidirectional"))
      (node (ref "U$3") (pin "P$3") (pinfunction "OUT2_P$3") (pintype "bidirectional"))
    )
    (net (code "97") (name "Net-(U$4-IN)") (class "Default")
      (node (ref "S$5") (pin "1") (pinfunction "1_1") (pintype "passive"))
      (node (ref "U$4") (pin "P$1") (pinfunction "IN_P$1") (pintype "bidirectional"))
    )
    (net (code "98") (name "Net-(U$4-OUT1)") (class "Default")
      (node (ref "U$4") (pin "P$2") (pinfunction "OUT1_P$2") (pintype "bidirectional"))
      (node (ref "U$5") (pin "P$1") (pinfunction "IN_P$1") (pintype "bidirectional"))
    )
    (net (code "99") (name "Net-(U$5-OUT1)") (class "Default")
      (node (ref "B$10") (pin "HF") (pinfunction "HF_HF") (pintype "bidirectional"))
      (node (ref "U$5") (pin "P$2") (pinfunction "OUT1_P$2") (pintype "bidirectional"))
    )
    (net (code "100") (name "Net-(U$5-OUT2)") (class "Default")
      (node (ref "B$9") (pin "HF") (pinfunction "HF_HF") (pintype "bidirectional"))
      (node (ref "U$5") (pin "P$3") (pinfunction "OUT2_P$3") (pintype "bidirectional"))
    )
    (net (code "101") (name "unconnected-(U$2-PadI$1)") (class "Default")
      (node (ref "U$2") (pin "I$1") (pinfunction "I$1_I$1") (pintype "bidirectional"))
    )
    (net (code "102") (name "unconnected-(U$2-PadI$2)") (class "Default")
      (node (ref "U$2") (pin "I$2") (pinfunction "I$2_I$2") (pintype "bidirectional"))
    )
    (net (code "103") (name "unconnected-(U$2-PadU$1)") (class "Default")
      (node (ref "U$2") (pin "U$1") (pinfunction "U$1_U$1") (pintype "bidirectional"))
    )
    (net (code "104") (name "unconnected-(U$2-PadU$2)") (class "Default")
      (node (ref "U$2") (pin "U$2") (pinfunction "U$2_U$2") (pintype "bidirectional"))
    )
  )
)
